# untitled.net
KiCad netlist of a schematic drawn in EAGLE
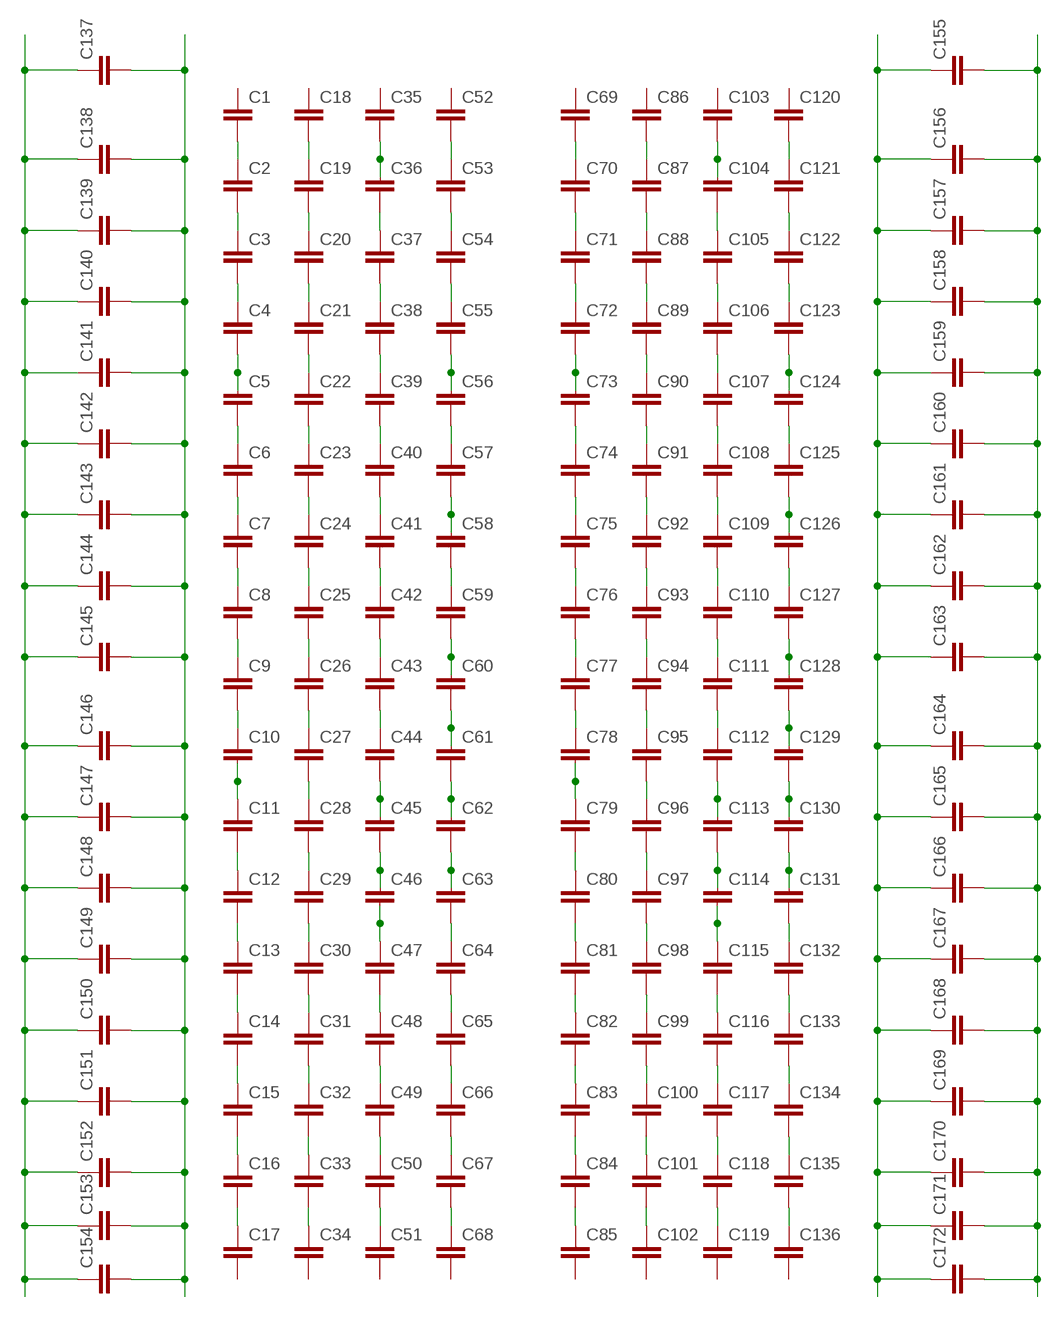
[diagram p0: schematic, sheet 1]

(export (version "E")
  (design (tool "Eeschema 10.0.6"))
  (components
    (comp (ref "C1")
      (value "C2,5-3")
      (footprint "eagle-import:C2.5-3")
      (libsource (lib "eagle-import") (part "C2,5-3"))
    )
    (comp (ref "C2")
      (value "C2,5-3")
      (footprint "eagle-import:C2.5-3")
      (libsource (lib "eagle-import") (part "C2,5-3"))
    )
    (comp (ref "C3")
      (value "C2,5-3")
      (footprint "eagle-import:C2.5-3")
      (libsource (lib "eagle-import") (part "C2,5-3"))
    )
    (comp (ref "C4")
      (value "C2,5-3")
      (footprint "eagle-import:C2.5-3")
      (libsource (lib "eagle-import") (part "C2,5-3"))
    )
    (comp (ref "C5")
      (value "C2,5-3")
      (footprint "eagle-import:C2.5-3")
      (libsource (lib "eagle-import") (part "C2,5-3"))
    )
    (comp (ref "C6")
      (value "C2,5-3")
      (footprint "eagle-import:C2.5-3")
      (libsource (lib "eagle-import") (part "C2,5-3"))
    )
    (comp (ref "C7")
      (value "C2,5-3")
      (footprint "eagle-import:C2.5-3")
      (libsource (lib "eagle-import") (part "C2,5-3"))
    )
    (comp (ref "C8")
      (value "C2,5-3")
      (footprint "eagle-import:C2.5-3")
      (libsource (lib "eagle-import") (part "C2,5-3"))
    )
    (comp (ref "C9")
      (value "C2,5-3")
      (footprint "eagle-import:C2.5-3")
      (libsource (lib "eagle-import") (part "C2,5-3"))
    )
    (comp (ref "C10")
      (value "C2,5-3")
      (footprint "eagle-import:C2.5-3")
      (libsource (lib "eagle-import") (part "C2,5-3"))
    )
    (comp (ref "C11")
      (value "C2,5-3")
      (footprint "eagle-import:C2.5-3")
      (libsource (lib "eagle-import") (part "C2,5-3"))
    )
    (comp (ref "C12")
      (value "C2,5-3")
      (footprint "eagle-import:C2.5-3")
      (libsource (lib "eagle-import") (part "C2,5-3"))
    )
    (comp (ref "C13")
      (value "C2,5-3")
      (footprint "eagle-import:C2.5-3")
      (libsource (lib "eagle-import") (part "C2,5-3"))
    )
    (comp (ref "C14")
      (value "C2,5-3")
      (footprint "eagle-import:C2.5-3")
      (libsource (lib "eagle-import") (part "C2,5-3"))
    )
    (comp (ref "C15")
      (value "C2,5-3")
      (footprint "eagle-import:C2.5-3")
      (libsource (lib "eagle-import") (part "C2,5-3"))
    )
    (comp (ref "C16")
      (value "C2,5-3")
      (footprint "eagle-import:C2.5-3")
      (libsource (lib "eagle-import") (part "C2,5-3"))
    )
    (comp (ref "C17")
      (value "C2,5-3")
      (footprint "eagle-import:C2.5-3")
      (libsource (lib "eagle-import") (part "C2,5-3"))
    )
    (comp (ref "C18")
      (value "C2,5-3")
      (footprint "eagle-import:C2.5-3")
      (libsource (lib "eagle-import") (part "C2,5-3"))
    )
    (comp (ref "C19")
      (value "C2,5-3")
      (footprint "eagle-import:C2.5-3")
      (libsource (lib "eagle-import") (part "C2,5-3"))
    )
    (comp (ref "C20")
      (value "C2,5-3")
      (footprint "eagle-import:C2.5-3")
      (libsource (lib "eagle-import") (part "C2,5-3"))
    )
    (comp (ref "C21")
      (value "C2,5-3")
      (footprint "eagle-import:C2.5-3")
      (libsource (lib "eagle-import") (part "C2,5-3"))
    )
    (comp (ref "C22")
      (value "C2,5-3")
      (footprint "eagle-import:C2.5-3")
      (libsource (lib "eagle-import") (part "C2,5-3"))
    )
    (comp (ref "C23")
      (value "C2,5-3")
      (footprint "eagle-import:C2.5-3")
      (libsource (lib "eagle-import") (part "C2,5-3"))
    )
    (comp (ref "C24")
      (value "C2,5-3")
      (footprint "eagle-import:C2.5-3")
      (libsource (lib "eagle-import") (part "C2,5-3"))
    )
    (comp (ref "C25")
      (value "C2,5-3")
      (footprint "eagle-import:C2.5-3")
      (libsource (lib "eagle-import") (part "C2,5-3"))
    )
    (comp (ref "C26")
      (value "C2,5-3")
      (footprint "eagle-import:C2.5-3")
      (libsource (lib "eagle-import") (part "C2,5-3"))
    )
    (comp (ref "C27")
      (value "C2,5-3")
      (footprint "eagle-import:C2.5-3")
      (libsource (lib "eagle-import") (part "C2,5-3"))
    )
    (comp (ref "C28")
      (value "C2,5-3")
      (footprint "eagle-import:C2.5-3")
      (libsource (lib "eagle-import") (part "C2,5-3"))
    )
    (comp (ref "C29")
      (value "C2,5-3")
      (footprint "eagle-import:C2.5-3")
      (libsource (lib "eagle-import") (part "C2,5-3"))
    )
    (comp (ref "C30")
      (value "C2,5-3")
      (footprint "eagle-import:C2.5-3")
      (libsource (lib "eagle-import") (part "C2,5-3"))
    )
    (comp (ref "C31")
      (value "C2,5-3")
      (footprint "eagle-import:C2.5-3")
      (libsource (lib "eagle-import") (part "C2,5-3"))
    )
    (comp (ref "C32")
      (value "C2,5-3")
      (footprint "eagle-import:C2.5-3")
      (libsource (lib "eagle-import") (part "C2,5-3"))
    )
    (comp (ref "C33")
      (value "C2,5-3")
      (footprint "eagle-import:C2.5-3")
      (libsource (lib "eagle-import") (part "C2,5-3"))
    )
    (comp (ref "C34")
      (value "C2,5-3")
      (footprint "eagle-import:C2.5-3")
      (libsource (lib "eagle-import") (part "C2,5-3"))
    )
    (comp (ref "C35")
      (value "C2,5-3")
      (footprint "eagle-import:C2.5-3")
      (libsource (lib "eagle-import") (part "C2,5-3"))
    )
    (comp (ref "C36")
      (value "C2,5-3")
      (footprint "eagle-import:C2.5-3")
      (libsource (lib "eagle-import") (part "C2,5-3"))
    )
    (comp (ref "C37")
      (value "C2,5-3")
      (footprint "eagle-import:C2.5-3")
      (libsource (lib "eagle-import") (part "C2,5-3"))
    )
    (comp (ref "C38")
      (value "C2,5-3")
      (footprint "eagle-import:C2.5-3")
      (libsource (lib "eagle-import") (part "C2,5-3"))
    )
    (comp (ref "C39")
      (value "C2,5-3")
      (footprint "eagle-import:C2.5-3")
      (libsource (lib "eagle-import") (part "C2,5-3"))
    )
    (comp (ref "C40")
      (value "C2,5-3")
      (footprint "eagle-import:C2.5-3")
      (libsource (lib "eagle-import") (part "C2,5-3"))
    )
    (comp (ref "C41")
      (value "C2,5-3")
      (footprint "eagle-import:C2.5-3")
      (libsource (lib "eagle-import") (part "C2,5-3"))
    )
    (comp (ref "C42")
      (value "C2,5-3")
      (footprint "eagle-import:C2.5-3")
      (libsource (lib "eagle-import") (part "C2,5-3"))
    )
    (comp (ref "C43")
      (value "C2,5-3")
      (footprint "eagle-import:C2.5-3")
      (libsource (lib "eagle-import") (part "C2,5-3"))
    )
    (comp (ref "C44")
      (value "C2,5-3")
      (footprint "eagle-import:C2.5-3")
      (libsource (lib "eagle-import") (part "C2,5-3"))
    )
    (comp (ref "C45")
      (value "C2,5-3")
      (footprint "eagle-import:C2.5-3")
      (libsource (lib "eagle-import") (part "C2,5-3"))
    )
    (comp (ref "C46")
      (value "C2,5-3")
      (footprint "eagle-import:C2.5-3")
      (libsource (lib "eagle-import") (part "C2,5-3"))
    )
    (comp (ref "C47")
      (value "C2,5-3")
      (footprint "eagle-import:C2.5-3")
      (libsource (lib "eagle-import") (part "C2,5-3"))
    )
    (comp (ref "C48")
      (value "C2,5-3")
      (footprint "eagle-import:C2.5-3")
      (libsource (lib "eagle-import") (part "C2,5-3"))
    )
    (comp (ref "C49")
      (value "C2,5-3")
      (footprint "eagle-import:C2.5-3")
      (libsource (lib "eagle-import") (part "C2,5-3"))
    )
    (comp (ref "C50")
      (value "C2,5-3")
      (footprint "eagle-import:C2.5-3")
      (libsource (lib "eagle-import") (part "C2,5-3"))
    )
    (comp (ref "C51")
      (value "C2,5-3")
      (footprint "eagle-import:C2.5-3")
      (libsource (lib "eagle-import") (part "C2,5-3"))
    )
    (comp (ref "C52")
      (value "C2,5-3")
      (footprint "eagle-import:C2.5-3")
      (libsource (lib "eagle-import") (part "C2,5-3"))
    )
    (comp (ref "C53")
      (value "C2,5-3")
      (footprint "eagle-import:C2.5-3")
      (libsource (lib "eagle-import") (part "C2,5-3"))
    )
    (comp (ref "C54")
      (value "C2,5-3")
      (footprint "eagle-import:C2.5-3")
      (libsource (lib "eagle-import") (part "C2,5-3"))
    )
    (comp (ref "C55")
      (value "C2,5-3")
      (footprint "eagle-import:C2.5-3")
      (libsource (lib "eagle-import") (part "C2,5-3"))
    )
    (comp (ref "C56")
      (value "C2,5-3")
      (footprint "eagle-import:C2.5-3")
      (libsource (lib "eagle-import") (part "C2,5-3"))
    )
    (comp (ref "C57")
      (value "C2,5-3")
      (footprint "eagle-import:C2.5-3")
      (libsource (lib "eagle-import") (part "C2,5-3"))
    )
    (comp (ref "C58")
      (value "C2,5-3")
      (footprint "eagle-import:C2.5-3")
      (libsource (lib "eagle-import") (part "C2,5-3"))
    )
    (comp (ref "C59")
      (value "C2,5-3")
      (footprint "eagle-import:C2.5-3")
      (libsource (lib "eagle-import") (part "C2,5-3"))
    )
    (comp (ref "C60")
      (value "C2,5-3")
      (footprint "eagle-import:C2.5-3")
      (libsource (lib "eagle-import") (part "C2,5-3"))
    )
    (comp (ref "C61")
      (value "C2,5-3")
      (footprint "eagle-import:C2.5-3")
      (libsource (lib "eagle-import") (part "C2,5-3"))
    )
    (comp (ref "C62")
      (value "C2,5-3")
      (footprint "eagle-import:C2.5-3")
      (libsource (lib "eagle-import") (part "C2,5-3"))
    )
    (comp (ref "C63")
      (value "C2,5-3")
      (footprint "eagle-import:C2.5-3")
      (libsource (lib "eagle-import") (part "C2,5-3"))
    )
    (comp (ref "C64")
      (value "C2,5-3")
      (footprint "eagle-import:C2.5-3")
      (libsource (lib "eagle-import") (part "C2,5-3"))
    )
    (comp (ref "C65")
      (value "C2,5-3")
      (footprint "eagle-import:C2.5-3")
      (libsource (lib "eagle-import") (part "C2,5-3"))
    )
    (comp (ref "C66")
      (value "C2,5-3")
      (footprint "eagle-import:C2.5-3")
      (libsource (lib "eagle-import") (part "C2,5-3"))
    )
    (comp (ref "C67")
      (value "C2,5-3")
      (footprint "eagle-import:C2.5-3")
      (libsource (lib "eagle-import") (part "C2,5-3"))
    )
    (comp (ref "C68")
      (value "C2,5-3")
      (footprint "eagle-import:C2.5-3")
      (libsource (lib "eagle-import") (part "C2,5-3"))
    )
    (comp (ref "C69")
      (value "C2,5-3")
      (footprint "eagle-import:C2.5-3")
      (libsource (lib "eagle-import") (part "C2,5-3"))
    )
    (comp (ref "C70")
      (value "C2,5-3")
      (footprint "eagle-import:C2.5-3")
      (libsource (lib "eagle-import") (part "C2,5-3"))
    )
    (comp (ref "C71")
      (value "C2,5-3")
      (footprint "eagle-import:C2.5-3")
      (libsource (lib "eagle-import") (part "C2,5-3"))
    )
    (comp (ref "C72")
      (value "C2,5-3")
      (footprint "eagle-import:C2.5-3")
      (libsource (lib "eagle-import") (part "C2,5-3"))
    )
    (comp (ref "C73")
      (value "C2,5-3")
      (footprint "eagle-import:C2.5-3")
      (libsource (lib "eagle-import") (part "C2,5-3"))
    )
    (comp (ref "C74")
      (value "C2,5-3")
      (footprint "eagle-import:C2.5-3")
      (libsource (lib "eagle-import") (part "C2,5-3"))
    )
    (comp (ref "C75")
      (value "C2,5-3")
      (footprint "eagle-import:C2.5-3")
      (libsource (lib "eagle-import") (part "C2,5-3"))
    )
    (comp (ref "C76")
      (value "C2,5-3")
      (footprint "eagle-import:C2.5-3")
      (libsource (lib "eagle-import") (part "C2,5-3"))
    )
    (comp (ref "C77")
      (value "C2,5-3")
      (footprint "eagle-import:C2.5-3")
      (libsource (lib "eagle-import") (part "C2,5-3"))
    )
    (comp (ref "C78")
      (value "C2,5-3")
      (footprint "eagle-import:C2.5-3")
      (libsource (lib "eagle-import") (part "C2,5-3"))
    )
    (comp (ref "C79")
      (value "C2,5-3")
      (footprint "eagle-import:C2.5-3")
      (libsource (lib "eagle-import") (part "C2,5-3"))
    )
    (comp (ref "C80")
      (value "C2,5-3")
      (footprint "eagle-import:C2.5-3")
      (libsource (lib "eagle-import") (part "C2,5-3"))
    )
    (comp (ref "C81")
      (value "C2,5-3")
      (footprint "eagle-import:C2.5-3")
      (libsource (lib "eagle-import") (part "C2,5-3"))
    )
    (comp (ref "C82")
      (value "C2,5-3")
      (footprint "eagle-import:C2.5-3")
      (libsource (lib "eagle-import") (part "C2,5-3"))
    )
    (comp (ref "C83")
      (value "C2,5-3")
      (footprint "eagle-import:C2.5-3")
      (libsource (lib "eagle-import") (part "C2,5-3"))
    )
    (comp (ref "C84")
      (value "C2,5-3")
      (footprint "eagle-import:C2.5-3")
      (libsource (lib "eagle-import") (part "C2,5-3"))
    )
    (comp (ref "C85")
      (value "C2,5-3")
      (footprint "eagle-import:C2.5-3")
      (libsource (lib "eagle-import") (part "C2,5-3"))
    )
    (comp (ref "C86")
      (value "C2,5-3")
      (footprint "eagle-import:C2.5-3")
      (libsource (lib "eagle-import") (part "C2,5-3"))
    )
    (comp (ref "C87")
      (value "C2,5-3")
      (footprint "eagle-import:C2.5-3")
      (libsource (lib "eagle-import") (part "C2,5-3"))
    )
    (comp (ref "C88")
      (value "C2,5-3")
      (footprint "eagle-import:C2.5-3")
      (libsource (lib "eagle-import") (part "C2,5-3"))
    )
    (comp (ref "C89")
      (value "C2,5-3")
      (footprint "eagle-import:C2.5-3")
      (libsource (lib "eagle-import") (part "C2,5-3"))
    )
    (comp (ref "C90")
      (value "C2,5-3")
      (footprint "eagle-import:C2.5-3")
      (libsource (lib "eagle-import") (part "C2,5-3"))
    )
    (comp (ref "C91")
      (value "C2,5-3")
      (footprint "eagle-import:C2.5-3")
      (libsource (lib "eagle-import") (part "C2,5-3"))
    )
    (comp (ref "C92")
      (value "C2,5-3")
      (footprint "eagle-import:C2.5-3")
      (libsource (lib "eagle-import") (part "C2,5-3"))
    )
    (comp (ref "C93")
      (value "C2,5-3")
      (footprint "eagle-import:C2.5-3")
      (libsource (lib "eagle-import") (part "C2,5-3"))
    )
    (comp (ref "C94")
      (value "C2,5-3")
      (footprint "eagle-import:C2.5-3")
      (libsource (lib "eagle-import") (part "C2,5-3"))
    )
    (comp (ref "C95")
      (value "C2,5-3")
      (footprint "eagle-import:C2.5-3")
      (libsource (lib "eagle-import") (part "C2,5-3"))
    )
    (comp (ref "C96")
      (value "C2,5-3")
      (footprint "eagle-import:C2.5-3")
      (libsource (lib "eagle-import") (part "C2,5-3"))
    )
    (comp (ref "C97")
      (value "C2,5-3")
      (footprint "eagle-import:C2.5-3")
      (libsource (lib "eagle-import") (part "C2,5-3"))
    )
    (comp (ref "C98")
      (value "C2,5-3")
      (footprint "eagle-import:C2.5-3")
      (libsource (lib "eagle-import") (part "C2,5-3"))
    )
    (comp (ref "C99")
      (value "C2,5-3")
      (footprint "eagle-import:C2.5-3")
      (libsource (lib "eagle-import") (part "C2,5-3"))
    )
    (comp (ref "C100")
      (value "C2,5-3")
      (footprint "eagle-import:C2.5-3")
      (libsource (lib "eagle-import") (part "C2,5-3"))
    )
    (comp (ref "C101")
      (value "C2,5-3")
      (footprint "eagle-import:C2.5-3")
      (libsource (lib "eagle-import") (part "C2,5-3"))
    )
    (comp (ref "C102")
      (value "C2,5-3")
      (footprint "eagle-import:C2.5-3")
      (libsource (lib "eagle-import") (part "C2,5-3"))
    )
    (comp (ref "C103")
      (value "C2,5-3")
      (footprint "eagle-import:C2.5-3")
      (libsource (lib "eagle-import") (part "C2,5-3"))
    )
    (comp (ref "C104")
      (value "C2,5-3")
      (footprint "eagle-import:C2.5-3")
      (libsource (lib "eagle-import") (part "C2,5-3"))
    )
    (comp (ref "C105")
      (value "C2,5-3")
      (footprint "eagle-import:C2.5-3")
      (libsource (lib "eagle-import") (part "C2,5-3"))
    )
    (comp (ref "C106")
      (value "C2,5-3")
      (footprint "eagle-import:C2.5-3")
      (libsource (lib "eagle-import") (part "C2,5-3"))
    )
    (comp (ref "C107")
      (value "C2,5-3")
      (footprint "eagle-import:C2.5-3")
      (libsource (lib "eagle-import") (part "C2,5-3"))
    )
    (comp (ref "C108")
      (value "C2,5-3")
      (footprint "eagle-import:C2.5-3")
      (libsource (lib "eagle-import") (part "C2,5-3"))
    )
    (comp (ref "C109")
      (value "C2,5-3")
      (footprint "eagle-import:C2.5-3")
      (libsource (lib "eagle-import") (part "C2,5-3"))
    )
    (comp (ref "C110")
      (value "C2,5-3")
      (footprint "eagle-import:C2.5-3")
      (libsource (lib "eagle-import") (part "C2,5-3"))
    )
    (comp (ref "C111")
      (value "C2,5-3")
      (footprint "eagle-import:C2.5-3")
      (libsource (lib "eagle-import") (part "C2,5-3"))
    )
    (comp (ref "C112")
      (value "C2,5-3")
      (footprint "eagle-import:C2.5-3")
      (libsource (lib "eagle-import") (part "C2,5-3"))
    )
    (comp (ref "C113")
      (value "C2,5-3")
      (footprint "eagle-import:C2.5-3")
      (libsource (lib "eagle-import") (part "C2,5-3"))
    )
    (comp (ref "C114")
      (value "C2,5-3")
      (footprint "eagle-import:C2.5-3")
      (libsource (lib "eagle-import") (part "C2,5-3"))
    )
    (comp (ref "C115")
      (value "C2,5-3")
      (footprint "eagle-import:C2.5-3")
      (libsource (lib "eagle-import") (part "C2,5-3"))
    )
    (comp (ref "C116")
      (value "C2,5-3")
      (footprint "eagle-import:C2.5-3")
      (libsource (lib "eagle-import") (part "C2,5-3"))
    )
    (comp (ref "C117")
      (value "C2,5-3")
      (footprint "eagle-import:C2.5-3")
      (libsource (lib "eagle-import") (part "C2,5-3"))
    )
    (comp (ref "C118")
      (value "C2,5-3")
      (footprint "eagle-import:C2.5-3")
      (libsource (lib "eagle-import") (part "C2,5-3"))
    )
    (comp (ref "C119")
      (value "C2,5-3")
      (footprint "eagle-import:C2.5-3")
      (libsource (lib "eagle-import") (part "C2,5-3"))
    )
    (comp (ref "C120")
      (value "C2,5-3")
      (footprint "eagle-import:C2.5-3")
      (libsource (lib "eagle-import") (part "C2,5-3"))
    )
    (comp (ref "C121")
      (value "C2,5-3")
      (footprint "eagle-import:C2.5-3")
      (libsource (lib "eagle-import") (part "C2,5-3"))
    )
    (comp (ref "C122")
      (value "C2,5-3")
      (footprint "eagle-import:C2.5-3")
      (libsource (lib "eagle-import") (part "C2,5-3"))
    )
    (comp (ref "C123")
      (value "C2,5-3")
      (footprint "eagle-import:C2.5-3")
      (libsource (lib "eagle-import") (part "C2,5-3"))
    )
    (comp (ref "C124")
      (value "C2,5-3")
      (footprint "eagle-import:C2.5-3")
      (libsource (lib "eagle-import") (part "C2,5-3"))
    )
    (comp (ref "C125")
      (value "C2,5-3")
      (footprint "eagle-import:C2.5-3")
      (libsource (lib "eagle-import") (part "C2,5-3"))
    )
    (comp (ref "C126")
      (value "C2,5-3")
      (footprint "eagle-import:C2.5-3")
      (libsource (lib "eagle-import") (part "C2,5-3"))
    )
    (comp (ref "C127")
      (value "C2,5-3")
      (footprint "eagle-import:C2.5-3")
      (libsource (lib "eagle-import") (part "C2,5-3"))
    )
    (comp (ref "C128")
      (value "C2,5-3")
      (footprint "eagle-import:C2.5-3")
      (libsource (lib "eagle-import") (part "C2,5-3"))
    )
    (comp (ref "C129")
      (value "C2,5-3")
      (footprint "eagle-import:C2.5-3")
      (libsource (lib "eagle-import") (part "C2,5-3"))
    )
    (comp (ref "C130")
      (value "C2,5-3")
      (footprint "eagle-import:C2.5-3")
      (libsource (lib "eagle-import") (part "C2,5-3"))
    )
    (comp (ref "C131")
      (value "C2,5-3")
      (footprint "eagle-import:C2.5-3")
      (libsource (lib "eagle-import") (part "C2,5-3"))
    )
    (comp (ref "C132")
      (value "C2,5-3")
      (footprint "eagle-import:C2.5-3")
      (libsource (lib "eagle-import") (part "C2,5-3"))
    )
    (comp (ref "C133")
      (value "C2,5-3")
      (footprint "eagle-import:C2.5-3")
      (libsource (lib "eagle-import") (part "C2,5-3"))
    )
    (comp (ref "C134")
      (value "C2,5-3")
      (footprint "eagle-import:C2.5-3")
      (libsource (lib "eagle-import") (part "C2,5-3"))
    )
    (comp (ref "C135")
      (value "C2,5-3")
      (footprint "eagle-import:C2.5-3")
      (libsource (lib "eagle-import") (part "C2,5-3"))
    )
    (comp (ref "C136")
      (value "C2,5-3")
      (footprint "eagle-import:C2.5-3")
      (libsource (lib "eagle-import") (part "C2,5-3"))
    )
    (comp (ref "C137")
      (value "C2,5-3")
      (footprint "eagle-import:C2.5-3")
      (libsource (lib "eagle-import") (part "C2,5-3"))
    )
    (comp (ref "C138")
      (value "C2,5-3")
      (footprint "eagle-import:C2.5-3")
      (libsource (lib "eagle-import") (part "C2,5-3"))
    )
    (comp (ref "C139")
      (value "C2,5-3")
      (footprint "eagle-import:C2.5-3")
      (libsource (lib "eagle-import") (part "C2,5-3"))
    )
    (comp (ref "C140")
      (value "C2,5-3")
      (footprint "eagle-import:C2.5-3")
      (libsource (lib "eagle-import") (part "C2,5-3"))
    )
    (comp (ref "C141")
      (value "C2,5-3")
      (footprint "eagle-import:C2.5-3")
      (libsource (lib "eagle-import") (part "C2,5-3"))
    )
    (comp (ref "C142")
      (value "C2,5-3")
      (footprint "eagle-import:C2.5-3")
      (libsource (lib "eagle-import") (part "C2,5-3"))
    )
    (comp (ref "C143")
      (value "C2,5-3")
      (footprint "eagle-import:C2.5-3")
      (libsource (lib "eagle-import") (part "C2,5-3"))
    )
    (comp (ref "C144")
      (value "C2,5-3")
      (footprint "eagle-import:C2.5-3")
      (libsource (lib "eagle-import") (part "C2,5-3"))
    )
    (comp (ref "C145")
      (value "C2,5-3")
      (footprint "eagle-import:C2.5-3")
      (libsource (lib "eagle-import") (part "C2,5-3"))
    )
    (comp (ref "C146")
      (value "C2,5-3")
      (footprint "eagle-import:C2.5-3")
      (libsource (lib "eagle-import") (part "C2,5-3"))
    )
    (comp (ref "C147")
      (value "C2,5-3")
      (footprint "eagle-import:C2.5-3")
      (libsource (lib "eagle-import") (part "C2,5-3"))
    )
    (comp (ref "C148")
      (value "C2,5-3")
      (footprint "eagle-import:C2.5-3")
      (libsource (lib "eagle-import") (part "C2,5-3"))
    )
    (comp (ref "C149")
      (value "C2,5-3")
      (footprint "eagle-import:C2.5-3")
      (libsource (lib "eagle-import") (part "C2,5-3"))
    )
    (comp (ref "C150")
      (value "C2,5-3")
      (footprint "eagle-import:C2.5-3")
      (libsource (lib "eagle-import") (part "C2,5-3"))
    )
    (comp (ref "C151")
      (value "C2,5-3")
      (footprint "eagle-import:C2.5-3")
      (libsource (lib "eagle-import") (part "C2,5-3"))
    )
    (comp (ref "C152")
      (value "C2,5-3")
      (footprint "eagle-import:C2.5-3")
      (libsource (lib "eagle-import") (part "C2,5-3"))
    )
    (comp (ref "C153")
      (value "C2,5-3")
      (footprint "eagle-import:C2.5-3")
      (libsource (lib "eagle-import") (part "C2,5-3"))
    )
    (comp (ref "C154")
      (value "C2,5-3")
      (footprint "eagle-import:C2.5-3")
      (libsource (lib "eagle-import") (part "C2,5-3"))
    )
    (comp (ref "C155")
      (value "C2,5-3")
      (footprint "eagle-import:C2.5-3")
      (libsource (lib "eagle-import") (part "C2,5-3"))
    )
    (comp (ref "C156")
      (value "C2,5-3")
      (footprint "eagle-import:C2.5-3")
      (libsource (lib "eagle-import") (part "C2,5-3"))
    )
    (comp (ref "C157")
      (value "C2,5-3")
      (footprint "eagle-import:C2.5-3")
      (libsource (lib "eagle-import") (part "C2,5-3"))
    )
    (comp (ref "C158")
      (value "C2,5-3")
      (footprint "eagle-import:C2.5-3")
      (libsource (lib "eagle-import") (part "C2,5-3"))
    )
    (comp (ref "C159")
      (value "C2,5-3")
      (footprint "eagle-import:C2.5-3")
      (libsource (lib "eagle-import") (part "C2,5-3"))
    )
    (comp (ref "C160")
      (value "C2,5-3")
      (footprint "eagle-import:C2.5-3")
      (libsource (lib "eagle-import") (part "C2,5-3"))
    )
    (comp (ref "C161")
      (value "C2,5-3")
      (footprint "eagle-import:C2.5-3")
      (libsource (lib "eagle-import") (part "C2,5-3"))
    )
    (comp (ref "C162")
      (value "C2,5-3")
      (footprint "eagle-import:C2.5-3")
      (libsource (lib "eagle-import") (part "C2,5-3"))
    )
    (comp (ref "C163")
      (value "C2,5-3")
      (footprint "eagle-import:C2.5-3")
      (libsource (lib "eagle-import") (part "C2,5-3"))
    )
    (comp (ref "C164")
      (value "C2,5-3")
      (footprint "eagle-import:C2.5-3")
      (libsource (lib "eagle-import") (part "C2,5-3"))
    )
    (comp (ref "C165")
      (value "C2,5-3")
      (footprint "eagle-import:C2.5-3")
      (libsource (lib "eagle-import") (part "C2,5-3"))
    )
    (comp (ref "C166")
      (value "C2,5-3")
      (footprint "eagle-import:C2.5-3")
      (libsource (lib "eagle-import") (part "C2,5-3"))
    )
    (comp (ref "C167")
      (value "C2,5-3")
      (footprint "eagle-import:C2.5-3")
      (libsource (lib "eagle-import") (part "C2,5-3"))
    )
    (comp (ref "C168")
      (value "C2,5-3")
      (footprint "eagle-import:C2.5-3")
      (libsource (lib "eagle-import") (part "C2,5-3"))
    )
    (comp (ref "C169")
      (value "C2,5-3")
      (footprint "eagle-import:C2.5-3")
      (libsource (lib "eagle-import") (part "C2,5-3"))
    )
    (comp (ref "C170")
      (value "C2,5-3")
      (footprint "eagle-import:C2.5-3")
      (libsource (lib "eagle-import") (part "C2,5-3"))
    )
    (comp (ref "C171")
      (value "C2,5-3")
      (footprint "eagle-import:C2.5-3")
      (libsource (lib "eagle-import") (part "C2,5-3"))
    )
    (comp (ref "C172")
      (value "C2,5-3")
      (footprint "eagle-import:C2.5-3")
      (libsource (lib "eagle-import") (part "C2,5-3"))
    )
  )
  (nets
    (net (code "1") (name "Net-(C1-Pad2)") (class "Default")
      (node (ref "C1") (pin "2") (pinfunction "2_2") (pintype "passive"))
      (node (ref "C2") (pin "1") (pinfunction "1_1") (pintype "passive"))
    )
    (net (code "2") (name "Net-(C2-Pad2)") (class "Default")
      (node (ref "C2") (pin "2") (pinfunction "2_2") (pintype "passive"))
      (node (ref "C3") (pin "1") (pinfunction "1_1") (pintype "passive"))
    )
    (net (code "3") (name "Net-(C3-Pad2)") (class "Default")
      (node (ref "C3") (pin "2") (pinfunction "2_2") (pintype "passive"))
      (node (ref "C4") (pin "1") (pinfunction "1_1") (pintype "passive"))
    )
    (net (code "4") (name "Net-(C4-Pad2)") (class "Default")
      (node (ref "C4") (pin "2") (pinfunction "2_2") (pintype "passive"))
      (node (ref "C5") (pin "1") (pinfunction "1_1") (pintype "passive"))
    )
    (net (code "5") (name "Net-(C5-Pad2)") (class "Default")
      (node (ref "C5") (pin "2") (pinfunction "2_2") (pintype "passive"))
      (node (ref "C6") (pin "1") (pinfunction "1_1") (pintype "passive"))
    )
    (net (code "6") (name "Net-(C6-Pad2)") (class "Default")
      (node (ref "C6") (pin "2") (pinfunction "2_2") (pintype "passive"))
      (node (ref "C7") (pin "1") (pinfunction "1_1") (pintype "passive"))
    )
    (net (code "7") (name "Net-(C7-Pad2)") (class "Default")
      (node (ref "C7") (pin "2") (pinfunction "2_2") (pintype "passive"))
      (node (ref "C8") (pin "1") (pinfunction "1_1") (pintype "passive"))
    )
    (net (code "8") (name "Net-(C8-Pad2)") (class "Default")
      (node (ref "C8") (pin "2") (pinfunction "2_2") (pintype "passive"))
      (node (ref "C9") (pin "1") (pinfunction "1_1") (pintype "passive"))
    )
    (net (code "9") (name "Net-(C10-Pad1)") (class "Default")
      (node (ref "C10") (pin "1") (pinfunction "1_1") (pintype "passive"))
      (node (ref "C9") (pin "2") (pinfunction "2_2") (pintype "passive"))
    )
    (net (code "10") (name "Net-(C10-Pad2)") (class "Default")
      (node (ref "C10") (pin "2") (pinfunction "2_2") (pintype "passive"))
      (node (ref "C11") (pin "1") (pinfunction "1_1") (pintype "passive"))
    )
    (net (code "11") (name "Net-(C11-Pad2)") (class "Default")
      (node (ref "C11") (pin "2") (pinfunction "2_2") (pintype "passive"))
      (node (ref "C12") (pin "1") (pinfunction "1_1") (pintype "passive"))
    )
    (net (code "12") (name "Net-(C12-Pad2)") (class "Default")
      (node (ref "C12") (pin "2") (pinfunction "2_2") (pintype "passive"))
      (node (ref "C13") (pin "1") (pinfunction "1_1") (pintype "passive"))
    )
    (net (code "13") (name "Net-(C13-Pad2)") (class "Default")
      (node (ref "C13") (pin "2") (pinfunction "2_2") (pintype "passive"))
      (node (ref "C14") (pin "1") (pinfunction "1_1") (pintype "passive"))
    )
    (net (code "14") (name "Net-(C14-Pad2)") (class "Default")
      (node (ref "C14") (pin "2") (pinfunction "2_2") (pintype "passive"))
      (node (ref "C15") (pin "1") (pinfunction "1_1") (pintype "passive"))
    )
    (net (code "15") (name "Net-(C15-Pad2)") (class "Default")
      (node (ref "C15") (pin "2") (pinfunction "2_2") (pintype "passive"))
      (node (ref "C16") (pin "1") (pinfunction "1_1") (pintype "passive"))
    )
    (net (code "16") (name "Net-(C16-Pad2)") (class "Default")
      (node (ref "C16") (pin "2") (pinfunction "2_2") (pintype "passive"))
      (node (ref "C17") (pin "1") (pinfunction "1_1") (pintype "passive"))
    )
    (net (code "17") (name "Net-(C18-Pad2)") (class "Default")
      (node (ref "C18") (pin "2") (pinfunction "2_2") (pintype "passive"))
      (node (ref "C19") (pin "1") (pinfunction "1_1") (pintype "passive"))
    )
    (net (code "18") (name "Net-(C19-Pad2)") (class "Default")
      (node (ref "C19") (pin "2") (pinfunction "2_2") (pintype "passive"))
      (node (ref "C20") (pin "1") (pinfunction "1_1") (pintype "passive"))
    )
    (net (code "19") (name "Net-(C20-Pad2)") (class "Default")
      (node (ref "C20") (pin "2") (pinfunction "2_2") (pintype "passive"))
      (node (ref "C21") (pin "1") (pinfunction "1_1") (pintype "passive"))
    )
    (net (code "20") (name "Net-(C21-Pad2)") (class "Default")
      (node (ref "C21") (pin "2") (pinfunction "2_2") (pintype "passive"))
      (node (ref "C22") (pin "1") (pinfunction "1_1") (pintype "passive"))
    )
    (net (code "21") (name "Net-(C22-Pad2)") (class "Default")
      (node (ref "C22") (pin "2") (pinfunction "2_2") (pintype "passive"))
      (node (ref "C23") (pin "1") (pinfunction "1_1") (pintype "passive"))
    )
    (net (code "22") (name "Net-(C23-Pad2)") (class "Default")
      (node (ref "C23") (pin "2") (pinfunction "2_2") (pintype "passive"))
      (node (ref "C24") (pin "1") (pinfunction "1_1") (pintype "passive"))
    )
    (net (code "23") (name "Net-(C24-Pad2)") (class "Default")
      (node (ref "C24") (pin "2") (pinfunction "2_2") (pintype "passive"))
      (node (ref "C25") (pin "1") (pinfunction "1_1") (pintype "passive"))
    )
    (net (code "24") (name "Net-(C25-Pad2)") (class "Default")
      (node (ref "C25") (pin "2") (pinfunction "2_2") (pintype "passive"))
      (node (ref "C26") (pin "1") (pinfunction "1_1") (pintype "passive"))
    )
    (net (code "25") (name "Net-(C26-Pad2)") (class "Default")
      (node (ref "C26") (pin "2") (pinfunction "2_2") (pintype "passive"))
      (node (ref "C27") (pin "1") (pinfunction "1_1") (pintype "passive"))
    )
    (net (code "26") (name "Net-(C27-Pad2)") (class "Default")
      (node (ref "C27") (pin "2") (pinfunction "2_2") (pintype "passive"))
      (node (ref "C28") (pin "1") (pinfunction "1_1") (pintype "passive"))
    )
    (net (code "27") (name "Net-(C28-Pad2)") (class "Default")
      (node (ref "C28") (pin "2") (pinfunction "2_2") (pintype "passive"))
      (node (ref "C29") (pin "1") (pinfunction "1_1") (pintype "passive"))
    )
    (net (code "28") (name "Net-(C29-Pad2)") (class "Default")
      (node (ref "C29") (pin "2") (pinfunction "2_2") (pintype "passive"))
      (node (ref "C30") (pin "1") (pinfunction "1_1") (pintype "passive"))
    )
    (net (code "29") (name "Net-(C30-Pad2)") (class "Default")
      (node (ref "C30") (pin "2") (pinfunction "2_2") (pintype "passive"))
      (node (ref "C31") (pin "1") (pinfunction "1_1") (pintype "passive"))
    )
    (net (code "30") (name "Net-(C31-Pad2)") (class "Default")
      (node (ref "C31") (pin "2") (pinfunction "2_2") (pintype "passive"))
      (node (ref "C32") (pin "1") (pinfunction "1_1") (pintype "passive"))
    )
    (net (code "31") (name "Net-(C32-Pad2)") (class "Default")
      (node (ref "C32") (pin "2") (pinfunction "2_2") (pintype "passive"))
      (node (ref "C33") (pin "1") (pinfunction "1_1") (pintype "passive"))
    )
    (net (code "32") (name "Net-(C33-Pad2)") (class "Default")
      (node (ref "C33") (pin "2") (pinfunction "2_2") (pintype "passive"))
      (node (ref "C34") (pin "1") (pinfunction "1_1") (pintype "passive"))
    )
    (net (code "33") (name "Net-(C35-Pad2)") (class "Default")
      (node (ref "C35") (pin "2") (pinfunction "2_2") (pintype "passive"))
      (node (ref "C36") (pin "1") (pinfunction "1_1") (pintype "passive"))
    )
    (net (code "34") (name "Net-(C36-Pad2)") (class "Default")
      (node (ref "C36") (pin "2") (pinfunction "2_2") (pintype "passive"))
      (node (ref "C37") (pin "1") (pinfunction "1_1") (pintype "passive"))
    )
    (net (code "35") (name "Net-(C37-Pad2)") (class "Default")
      (node (ref "C37") (pin "2") (pinfunction "2_2") (pintype "passive"))
      (node (ref "C38") (pin "1") (pinfunction "1_1") (pintype "passive"))
    )
    (net (code "36") (name "Net-(C38-Pad2)") (class "Default")
      (node (ref "C38") (pin "2") (pinfunction "2_2") (pintype "passive"))
      (node (ref "C39") (pin "1") (pinfunction "1_1") (pintype "passive"))
    )
    (net (code "37") (name "Net-(C39-Pad2)") (class "Default")
      (node (ref "C39") (pin "2") (pinfunction "2_2") (pintype "passive"))
      (node (ref "C40") (pin "1") (pinfunction "1_1") (pintype "passive"))
    )
    (net (code "38") (name "Net-(C40-Pad2)") (class "Default")
      (node (ref "C40") (pin "2") (pinfunction "2_2") (pintype "passive"))
      (node (ref "C41") (pin "1") (pinfunction "1_1") (pintype "passive"))
    )
    (net (code "39") (name "Net-(C41-Pad2)") (class "Default")
      (node (ref "C41") (pin "2") (pinfunction "2_2") (pintype "passive"))
      (node (ref "C42") (pin "1") (pinfunction "1_1") (pintype "passive"))
    )
    (net (code "40") (name "Net-(C42-Pad2)") (class "Default")
      (node (ref "C42") (pin "2") (pinfunction "2_2") (pintype "passive"))
      (node (ref "C43") (pin "1") (pinfunction "1_1") (pintype "passive"))
    )
    (net (code "41") (name "Net-(C43-Pad2)") (class "Default")
      (node (ref "C43") (pin "2") (pinfunction "2_2") (pintype "passive"))
      (node (ref "C44") (pin "1") (pinfunction "1_1") (pintype "passive"))
    )
    (net (code "42") (name "Net-(C44-Pad2)") (class "Default")
      (node (ref "C44") (pin "2") (pinfunction "2_2") (pintype "passive"))
      (node (ref "C45") (pin "1") (pinfunction "1_1") (pintype "passive"))
    )
    (net (code "43") (name "Net-(C45-Pad2)") (class "Default")
      (node (ref "C45") (pin "2") (pinfunction "2_2") (pintype "passive"))
      (node (ref "C46") (pin "1") (pinfunction "1_1") (pintype "passive"))
    )
    (net (code "44") (name "Net-(C46-Pad2)") (class "Default")
      (node (ref "C46") (pin "2") (pinfunction "2_2") (pintype "passive"))
      (node (ref "C47") (pin "1") (pinfunction "1_1") (pintype "passive"))
    )
    (net (code "45") (name "Net-(C47-Pad2)") (class "Default")
      (node (ref "C47") (pin "2") (pinfunction "2_2") (pintype "passive"))
      (node (ref "C48") (pin "1") (pinfunction "1_1") (pintype "passive"))
    )
    (net (code "46") (name "Net-(C48-Pad2)") (class "Default")
      (node (ref "C48") (pin "2") (pinfunction "2_2") (pintype "passive"))
      (node (ref "C49") (pin "1") (pinfunction "1_1") (pintype "passive"))
    )
    (net (code "47") (name "Net-(C49-Pad2)") (class "Default")
      (node (ref "C49") (pin "2") (pinfunction "2_2") (pintype "passive"))
      (node (ref "C50") (pin "1") (pinfunction "1_1") (pintype "passive"))
    )
    (net (code "48") (name "Net-(C50-Pad2)") (class "Default")
      (node (ref "C50") (pin "2") (pinfunction "2_2") (pintype "passive"))
      (node (ref "C51") (pin "1") (pinfunction "1_1") (pintype "passive"))
    )
    (net (code "49") (name "Net-(C52-Pad2)") (class "Default")
      (node (ref "C52") (pin "2") (pinfunction "2_2") (pintype "passive"))
      (node (ref "C53") (pin "1") (pinfunction "1_1") (pintype "passive"))
    )
    (net (code "50") (name "Net-(C53-Pad2)") (class "Default")
      (node (ref "C53") (pin "2") (pinfunction "2_2") (pintype "passive"))
      (node (ref "C54") (pin "1") (pinfunction "1_1") (pintype "passive"))
    )
    (net (code "51") (name "Net-(C54-Pad2)") (class "Default")
      (node (ref "C54") (pin "2") (pinfunction "2_2") (pintype "passive"))
      (node (ref "C55") (pin "1") (pinfunction "1_1") (pintype "passive"))
    )
    (net (code "52") (name "Net-(C55-Pad2)") (class "Default")
      (node (ref "C55") (pin "2") (pinfunction "2_2") (pintype "passive"))
      (node (ref "C56") (pin "1") (pinfunction "1_1") (pintype "passive"))
    )
    (net (code "53") (name "Net-(C56-Pad2)") (class "Default")
      (node (ref "C56") (pin "2") (pinfunction "2_2") (pintype "passive"))
      (node (ref "C57") (pin "1") (pinfunction "1_1") (pintype "passive"))
    )
    (net (code "54") (name "Net-(C57-Pad2)") (class "Default")
      (node (ref "C57") (pin "2") (pinfunction "2_2") (pintype "passive"))
      (node (ref "C58") (pin "1") (pinfunction "1_1") (pintype "passive"))
    )
    (net (code "55") (name "Net-(C58-Pad2)") (class "Default")
      (node (ref "C58") (pin "2") (pinfunction "2_2") (pintype "passive"))
      (node (ref "C59") (pin "1") (pinfunction "1_1") (pintype "passive"))
    )
    (net (code "56") (name "Net-(C59-Pad2)") (class "Default")
      (node (ref "C59") (pin "2") (pinfunction "2_2") (pintype "passive"))
      (node (ref "C60") (pin "1") (pinfunction "1_1") (pintype "passive"))
    )
    (net (code "57") (name "Net-(C60-Pad2)") (class "Default")
      (node (ref "C60") (pin "2") (pinfunction "2_2") (pintype "passive"))
      (node (ref "C61") (pin "1") (pinfunction "1_1") (pintype "passive"))
    )
    (net (code "58") (name "Net-(C61-Pad2)") (class "Default")
      (node (ref "C61") (pin "2") (pinfunction "2_2") (pintype "passive"))
      (node (ref "C62") (pin "1") (pinfunction "1_1") (pintype "passive"))
    )
    (net (code "59") (name "Net-(C62-Pad2)") (class "Default")
      (node (ref "C62") (pin "2") (pinfunction "2_2") (pintype "passive"))
      (node (ref "C63") (pin "1") (pinfunction "1_1") (pintype "passive"))
    )
    (net (code "60") (name "Net-(C63-Pad2)") (class "Default")
      (node (ref "C63") (pin "2") (pinfunction "2_2") (pintype "passive"))
      (node (ref "C64") (pin "1") (pinfunction "1_1") (pintype "passive"))
    )
    (net (code "61") (name "Net-(C64-Pad2)") (class "Default")
      (node (ref "C64") (pin "2") (pinfunction "2_2") (pintype "passive"))
      (node (ref "C65") (pin "1") (pinfunction "1_1") (pintype "passive"))
    )
    (net (code "62") (name "Net-(C65-Pad2)") (class "Default")
      (node (ref "C65") (pin "2") (pinfunction "2_2") (pintype "passive"))
      (node (ref "C66") (pin "1") (pinfunction "1_1") (pintype "passive"))
    )
    (net (code "63") (name "Net-(C66-Pad2)") (class "Default")
      (node (ref "C66") (pin "2") (pinfunction "2_2") (pintype "passive"))
      (node (ref "C67") (pin "1") (pinfunction "1_1") (pintype "passive"))
    )
    (net (code "64") (name "Net-(C67-Pad2)") (class "Default")
      (node (ref "C67") (pin "2") (pinfunction "2_2") (pintype "passive"))
      (node (ref "C68") (pin "1") (pinfunction "1_1") (pintype "passive"))
    )
    (net (code "65") (name "Net-(C69-Pad2)") (class "Default")
      (node (ref "C69") (pin "2") (pinfunction "2_2") (pintype "passive"))
      (node (ref "C70") (pin "1") (pinfunction "1_1") (pintype "passive"))
    )
    (net (code "66") (name "Net-(C70-Pad2)") (class "Default")
      (node (ref "C70") (pin "2") (pinfunction "2_2") (pintype "passive"))
      (node (ref "C71") (pin "1") (pinfunction "1_1") (pintype "passive"))
    )
    (net (code "67") (name "Net-(C71-Pad2)") (class "Default")
      (node (ref "C71") (pin "2") (pinfunction "2_2") (pintype "passive"))
      (node (ref "C72") (pin "1") (pinfunction "1_1") (pintype "passive"))
    )
    (net (code "68") (name "Net-(C72-Pad2)") (class "Default")
      (node (ref "C72") (pin "2") (pinfunction "2_2") (pintype "passive"))
      (node (ref "C73") (pin "1") (pinfunction "1_1") (pintype "passive"))
    )
    (net (code "69") (name "Net-(C73-Pad2)") (class "Default")
      (node (ref "C73") (pin "2") (pinfunction "2_2") (pintype "passive"))
      (node (ref "C74") (pin "1") (pinfunction "1_1") (pintype "passive"))
    )
    (net (code "70") (name "Net-(C74-Pad2)") (class "Default")
      (node (ref "C74") (pin "2") (pinfunction "2_2") (pintype "passive"))
      (node (ref "C75") (pin "1") (pinfunction "1_1") (pintype "passive"))
    )
    (net (code "71") (name "Net-(C75-Pad2)") (class "Default")
      (node (ref "C75") (pin "2") (pinfunction "2_2") (pintype "passive"))
      (node (ref "C76") (pin "1") (pinfunction "1_1") (pintype "passive"))
    )
    (net (code "72") (name "Net-(C76-Pad2)") (class "Default")
      (node (ref "C76") (pin "2") (pinfunction "2_2") (pintype "passive"))
      (node (ref "C77") (pin "1") (pinfunction "1_1") (pintype "passive"))
    )
    (net (code "73") (name "Net-(C77-Pad2)") (class "Default")
      (node (ref "C77") (pin "2") (pinfunction "2_2") (pintype "passive"))
      (node (ref "C78") (pin "1") (pinfunction "1_1") (pintype "passive"))
    )
    (net (code "74") (name "Net-(C78-Pad2)") (class "Default")
      (node (ref "C78") (pin "2") (pinfunction "2_2") (pintype "passive"))
      (node (ref "C79") (pin "1") (pinfunction "1_1") (pintype "passive"))
    )
    (net (code "75") (name "Net-(C79-Pad2)") (class "Default")
      (node (ref "C79") (pin "2") (pinfunction "2_2") (pintype "passive"))
      (node (ref "C80") (pin "1") (pinfunction "1_1") (pintype "passive"))
    )
    (net (code "76") (name "Net-(C80-Pad2)") (class "Default")
      (node (ref "C80") (pin "2") (pinfunction "2_2") (pintype "passive"))
      (node (ref "C81") (pin "1") (pinfunction "1_1") (pintype "passive"))
    )
    (net (code "77") (name "Net-(C81-Pad2)") (class "Default")
      (node (ref "C81") (pin "2") (pinfunction "2_2") (pintype "passive"))
      (node (ref "C82") (pin "1") (pinfunction "1_1") (pintype "passive"))
    )
    (net (code "78") (name "Net-(C82-Pad2)") (class "Default")
      (node (ref "C82") (pin "2") (pinfunction "2_2") (pintype "passive"))
      (node (ref "C83") (pin "1") (pinfunction "1_1") (pintype "passive"))
    )
    (net (code "79") (name "Net-(C83-Pad2)") (class "Default")
      (node (ref "C83") (pin "2") (pinfunction "2_2") (pintype "passive"))
      (node (ref "C84") (pin "1") (pinfunction "1_1") (pintype "passive"))
    )
    (net (code "80") (name "Net-(C84-Pad2)") (class "Default")
      (node (ref "C84") (pin "2") (pinfunction "2_2") (pintype "passive"))
      (node (ref "C85") (pin "1") (pinfunction "1_1") (pintype "passive"))
    )
    (net (code "81") (name "Net-(C86-Pad2)") (class "Default")
      (node (ref "C86") (pin "2") (pinfunction "2_2") (pintype "passive"))
      (node (ref "C87") (pin "1") (pinfunction "1_1") (pintype "passive"))
    )
    (net (code "82") (name "Net-(C87-Pad2)") (class "Default")
      (node (ref "C87") (pin "2") (pinfunction "2_2") (pintype "passive"))
      (node (ref "C88") (pin "1") (pinfunction "1_1") (pintype "passive"))
    )
    (net (code "83") (name "Net-(C88-Pad2)") (class "Default")
      (node (ref "C88") (pin "2") (pinfunction "2_2") (pintype "passive"))
      (node (ref "C89") (pin "1") (pinfunction "1_1") (pintype "passive"))
    )
    (net (code "84") (name "Net-(C89-Pad2)") (class "Default")
      (node (ref "C89") (pin "2") (pinfunction "2_2") (pintype "passive"))
      (node (ref "C90") (pin "1") (pinfunction "1_1") (pintype "passive"))
    )
    (net (code "85") (name "Net-(C90-Pad2)") (class "Default")
      (node (ref "C90") (pin "2") (pinfunction "2_2") (pintype "passive"))
      (node (ref "C91") (pin "1") (pinfunction "1_1") (pintype "passive"))
    )
    (net (code "86") (name "Net-(C91-Pad2)") (class "Default")
      (node (ref "C91") (pin "2") (pinfunction "2_2") (pintype "passive"))
      (node (ref "C92") (pin "1") (pinfunction "1_1") (pintype "passive"))
    )
    (net (code "87") (name "Net-(C92-Pad2)") (class "Default")
      (node (ref "C92") (pin "2") (pinfunction "2_2") (pintype "passive"))
      (node (ref "C93") (pin "1") (pinfunction "1_1") (pintype "passive"))
    )
    (net (code "88") (name "Net-(C93-Pad2)") (class "Default")
      (node (ref "C93") (pin "2") (pinfunction "2_2") (pintype "passive"))
      (node (ref "C94") (pin "1") (pinfunction "1_1") (pintype "passive"))
    )
    (net (code "89") (name "Net-(C94-Pad2)") (class "Default")
      (node (ref "C94") (pin "2") (pinfunction "2_2") (pintype "passive"))
      (node (ref "C95") (pin "1") (pinfunction "1_1") (pintype "passive"))
    )
    (net (code "90") (name "Net-(C95-Pad2)") (class "Default")
      (node (ref "C95") (pin "2") (pinfunction "2_2") (pintype "passive"))
      (node (ref "C96") (pin "1") (pinfunction "1_1") (pintype "passive"))
    )
    (net (code "91") (name "Net-(C96-Pad2)") (class "Default")
      (node (ref "C96") (pin "2") (pinfunction "2_2") (pintype "passive"))
      (node (ref "C97") (pin "1") (pinfunction "1_1") (pintype "passive"))
    )
    (net (code "92") (name "Net-(C97-Pad2)") (class "Default")
      (node (ref "C97") (pin "2") (pinfunction "2_2") (pintype "passive"))
      (node (ref "C98") (pin "1") (pinfunction "1_1") (pintype "passive"))
    )
    (net (code "93") (name "Net-(C98-Pad2)") (class "Default")
      (node (ref "C98") (pin "2") (pinfunction "2_2") (pintype "passive"))
      (node (ref "C99") (pin "1") (pinfunction "1_1") (pintype "passive"))
    )
    (net (code "94") (name "Net-(C100-Pad1)") (class "Default")
      (node (ref "C100") (pin "1") (pinfunction "1_1") (pintype "passive"))
      (node (ref "C99") (pin "2") (pinfunction "2_2") (pintype "passive"))
    )
    (net (code "95") (name "Net-(C100-Pad2)") (class "Default")
      (node (ref "C100") (pin "2") (pinfunction "2_2") (pintype "passive"))
      (node (ref "C101") (pin "1") (pinfunction "1_1") (pintype "passive"))
    )
    (net (code "96") (name "Net-(C101-Pad2)") (class "Default")
      (node (ref "C101") (pin "2") (pinfunction "2_2") (pintype "passive"))
      (node (ref "C102") (pin "1") (pinfunction "1_1") (pintype "passive"))
    )
    (net (code "97") (name "Net-(C103-Pad2)") (class "Default")
      (node (ref "C103") (pin "2") (pinfunction "2_2") (pintype "passive"))
      (node (ref "C104") (pin "1") (pinfunction "1_1") (pintype "passive"))
    )
    (net (code "98") (name "Net-(C104-Pad2)") (class "Default")
      (node (ref "C104") (pin "2") (pinfunction "2_2") (pintype "passive"))
      (node (ref "C105") (pin "1") (pinfunction "1_1") (pintype "passive"))
    )
    (net (code "99") (name "Net-(C105-Pad2)") (class "Default")
      (node (ref "C105") (pin "2") (pinfunction "2_2") (pintype "passive"))
      (node (ref "C106") (pin "1") (pinfunction "1_1") (pintype "passive"))
    )
    (net (code "100") (name "Net-(C106-Pad2)") (class "Default")
      (node (ref "C106") (pin "2") (pinfunction "2_2") (pintype "passive"))
      (node (ref "C107") (pin "1") (pinfunction "1_1") (pintype "passive"))
    )
    (net (code "101") (name "Net-(C107-Pad2)") (class "Default")
      (node (ref "C107") (pin "2") (pinfunction "2_2") (pintype "passive"))
      (node (ref "C108") (pin "1") (pinfunction "1_1") (pintype "passive"))
    )
    (net (code "102") (name "Net-(C108-Pad2)") (class "Default")
      (node (ref "C108") (pin "2") (pinfunction "2_2") (pintype "passive"))
      (node (ref "C109") (pin "1") (pinfunction "1_1") (pintype "passive"))
    )
    (net (code "103") (name "Net-(C109-Pad2)") (class "Default")
      (node (ref "C109") (pin "2") (pinfunction "2_2") (pintype "passive"))
      (node (ref "C110") (pin "1") (pinfunction "1_1") (pintype "passive"))
    )
    (net (code "104") (name "Net-(C110-Pad2)") (class "Default")
      (node (ref "C110") (pin "2") (pinfunction "2_2") (pintype "passive"))
      (node (ref "C111") (pin "1") (pinfunction "1_1") (pintype "passive"))
    )
    (net (code "105") (name "Net-(C111-Pad2)") (class "Default")
      (node (ref "C111") (pin "2") (pinfunction "2_2") (pintype "passive"))
      (node (ref "C112") (pin "1") (pinfunction "1_1") (pintype "passive"))
    )
    (net (code "106") (name "Net-(C112-Pad2)") (class "Default")
      (node (ref "C112") (pin "2") (pinfunction "2_2") (pintype "passive"))
      (node (ref "C113") (pin "1") (pinfunction "1_1") (pintype "passive"))
    )
    (net (code "107") (name "Net-(C113-Pad2)") (class "Default")
      (node (ref "C113") (pin "2") (pinfunction "2_2") (pintype "passive"))
      (node (ref "C114") (pin "1") (pinfunction "1_1") (pintype "passive"))
    )
    (net (code "108") (name "Net-(C114-Pad2)") (class "Default")
      (node (ref "C114") (pin "2") (pinfunction "2_2") (pintype "passive"))
      (node (ref "C115") (pin "1") (pinfunction "1_1") (pintype "passive"))
    )
    (net (code "109") (name "Net-(C115-Pad2)") (class "Default")
      (node (ref "C115") (pin "2") (pinfunction "2_2") (pintype "passive"))
      (node (ref "C116") (pin "1") (pinfunction "1_1") (pintype "passive"))
    )
    (net (code "110") (name "Net-(C116-Pad2)") (class "Default")
      (node (ref "C116") (pin "2") (pinfunction "2_2") (pintype "passive"))
      (node (ref "C117") (pin "1") (pinfunction "1_1") (pintype "passive"))
    )
    (net (code "111") (name "Net-(C117-Pad2)") (class "Default")
      (node (ref "C117") (pin "2") (pinfunction "2_2") (pintype "passive"))
      (node (ref "C118") (pin "1") (pinfunction "1_1") (pintype "passive"))
    )
    (net (code "112") (name "Net-(C118-Pad2)") (class "Default")
      (node (ref "C118") (pin "2") (pinfunction "2_2") (pintype "passive"))
      (node (ref "C119") (pin "1") (pinfunction "1_1") (pintype "passive"))
    )
    (net (code "113") (name "Net-(C120-Pad2)") (class "Default")
      (node (ref "C120") (pin "2") (pinfunction "2_2") (pintype "passive"))
      (node (ref "C121") (pin "1") (pinfunction "1_1") (pintype "passive"))
    )
    (net (code "114") (name "Net-(C121-Pad2)") (class "Default")
      (node (ref "C121") (pin "2") (pinfunction "2_2") (pintype "passive"))
      (node (ref "C122") (pin "1") (pinfunction "1_1") (pintype "passive"))
    )
    (net (code "115") (name "Net-(C122-Pad2)") (class "Default")
      (node (ref "C122") (pin "2") (pinfunction "2_2") (pintype "passive"))
      (node (ref "C123") (pin "1") (pinfunction "1_1") (pintype "passive"))
    )
    (net (code "116") (name "Net-(C123-Pad2)") (class "Default")
      (node (ref "C123") (pin "2") (pinfunction "2_2") (pintype "passive"))
      (node (ref "C124") (pin "1") (pinfunction "1_1") (pintype "passive"))
    )
    (net (code "117") (name "Net-(C124-Pad2)") (class "Default")
      (node (ref "C124") (pin "2") (pinfunction "2_2") (pintype "passive"))
      (node (ref "C125") (pin "1") (pinfunction "1_1") (pintype "passive"))
    )
    (net (code "118") (name "Net-(C125-Pad2)") (class "Default")
      (node (ref "C125") (pin "2") (pinfunction "2_2") (pintype "passive"))
      (node (ref "C126") (pin "1") (pinfunction "1_1") (pintype "passive"))
    )
    (net (code "119") (name "Net-(C126-Pad2)") (class "Default")
      (node (ref "C126") (pin "2") (pinfunction "2_2") (pintype "passive"))
      (node (ref "C127") (pin "1") (pinfunction "1_1") (pintype "passive"))
    )
    (net (code "120") (name "Net-(C127-Pad2)") (class "Default")
      (node (ref "C127") (pin "2") (pinfunction "2_2") (pintype "passive"))
      (node (ref "C128") (pin "1") (pinfunction "1_1") (pintype "passive"))
    )
    (net (code "121") (name "Net-(C128-Pad2)") (class "Default")
      (node (ref "C128") (pin "2") (pinfunction "2_2") (pintype "passive"))
      (node (ref "C129") (pin "1") (pinfunction "1_1") (pintype "passive"))
    )
    (net (code "122") (name "Net-(C129-Pad2)") (class "Default")
      (node (ref "C129") (pin "2") (pinfunction "2_2") (pintype "passive"))
      (node (ref "C130") (pin "1") (pinfunction "1_1") (pintype "passive"))
    )
    (net (code "123") (name "Net-(C130-Pad2)") (class "Default")
      (node (ref "C130") (pin "2") (pinfunction "2_2") (pintype "passive"))
      (node (ref "C131") (pin "1") (pinfunction "1_1") (pintype "passive"))
    )
    (net (code "124") (name "Net-(C131-Pad2)") (class "Default")
      (node (ref "C131") (pin "2") (pinfunction "2_2") (pintype "passive"))
      (node (ref "C132") (pin "1") (pinfunction "1_1") (pintype "passive"))
    )
    (net (code "125") (name "Net-(C132-Pad2)") (class "Default")
      (node (ref "C132") (pin "2") (pinfunction "2_2") (pintype "passive"))
      (node (ref "C133") (pin "1") (pinfunction "1_1") (pintype "passive"))
    )
    (net (code "126") (name "Net-(C133-Pad2)") (class "Default")
      (node (ref "C133") (pin "2") (pinfunction "2_2") (pintype "passive"))
      (node (ref "C134") (pin "1") (pinfunction "1_1") (pintype "passive"))
    )
    (net (code "127") (name "Net-(C134-Pad2)") (class "Default")
      (node (ref "C134") (pin "2") (pinfunction "2_2") (pintype "passive"))
      (node (ref "C135") (pin "1") (pinfunction "1_1") (pintype "passive"))
    )
    (net (code "128") (name "Net-(C135-Pad2)") (class "Default")
      (node (ref "C135") (pin "2") (pinfunction "2_2") (pintype "passive"))
      (node (ref "C136") (pin "1") (pinfunction "1_1") (pintype "passive"))
    )
    (net (code "129") (name "Net-(C137-Pad1)") (class "Default")
      (node (ref "C137") (pin "1") (pinfunction "1_1") (pintype "passive"))
      (node (ref "C138") (pin "1") (pinfunction "1_1") (pintype "passive"))
      (node (ref "C139") (pin "1") (pinfunction "1_1") (pintype "passive"))
      (node (ref "C140") (pin "1") (pinfunction "1_1") (pintype "passive"))
      (node (ref "C141") (pin "1") (pinfunction "1_1") (pintype "passive"))
      (node (ref "C142") (pin "1") (pinfunction "1_1") (pintype "passive"))
      (node (ref "C143") (pin "1") (pinfunction "1_1") (pintype "passive"))
      (node (ref "C144") (pin "1") (pinfunction "1_1") (pintype "passive"))
      (node (ref "C145") (pin "1") (pinfunction "1_1") (pintype "passive"))
      (node (ref "C146") (pin "1") (pinfunction "1_1") (pintype "passive"))
      (node (ref "C147") (pin "1") (pinfunction "1_1") (pintype "passive"))
      (node (ref "C148") (pin "1") (pinfunction "1_1") (pintype "passive"))
      (node (ref "C149") (pin "1") (pinfunction "1_1") (pintype "passive"))
      (node (ref "C150") (pin "1") (pinfunction "1_1") (pintype "passive"))
      (node (ref "C151") (pin "1") (pinfunction "1_1") (pintype "passive"))
      (node (ref "C152") (pin "1") (pinfunction "1_1") (pintype "passive"))
      (node (ref "C153") (pin "1") (pinfunction "1_1") (pintype "passive"))
      (node (ref "C154") (pin "1") (pinfunction "1_1") (pintype "passive"))
    )
    (net (code "130") (name "Net-(C137-Pad2)") (class "Default")
      (node (ref "C137") (pin "2") (pinfunction "2_2") (pintype "passive"))
      (node (ref "C138") (pin "2") (pinfunction "2_2") (pintype "passive"))
      (node (ref "C139") (pin "2") (pinfunction "2_2") (pintype "passive"))
      (node (ref "C140") (pin "2") (pinfunction "2_2") (pintype "passive"))
      (node (ref "C141") (pin "2") (pinfunction "2_2") (pintype "passive"))
      (node (ref "C142") (pin "2") (pinfunction "2_2") (pintype "passive"))
      (node (ref "C143") (pin "2") (pinfunction "2_2") (pintype "passive"))
      (node (ref "C144") (pin "2") (pinfunction "2_2") (pintype "passive"))
      (node (ref "C145") (pin "2") (pinfunction "2_2") (pintype "passive"))
      (node (ref "C146") (pin "2") (pinfunction "2_2") (pintype "passive"))
      (node (ref "C147") (pin "2") (pinfunction "2_2") (pintype "passive"))
      (node (ref "C148") (pin "2") (pinfunction "2_2") (pintype "passive"))
      (node (ref "C149") (pin "2") (pinfunction "2_2") (pintype "passive"))
      (node (ref "C150") (pin "2") (pinfunction "2_2") (pintype "passive"))
      (node (ref "C151") (pin "2") (pinfunction "2_2") (pintype "passive"))
      (node (ref "C152") (pin "2") (pinfunction "2_2") (pintype "passive"))
      (node (ref "C153") (pin "2") (pinfunction "2_2") (pintype "passive"))
      (node (ref "C154") (pin "2") (pinfunction "2_2") (pintype "passive"))
    )
    (net (code "131") (name "Net-(C155-Pad1)") (class "Default")
      (node (ref "C155") (pin "1") (pinfunction "1_1") (pintype "passive"))
      (node (ref "C156") (pin "1") (pinfunction "1_1") (pintype "passive"))
      (node (ref "C157") (pin "1") (pinfunction "1_1") (pintype "passive"))
      (node (ref "C158") (pin "1") (pinfunction "1_1") (pintype "passive"))
      (node (ref "C159") (pin "1") (pinfunction "1_1") (pintype "passive"))
      (node (ref "C160") (pin "1") (pinfunction "1_1") (pintype "passive"))
      (node (ref "C161") (pin "1") (pinfunction "1_1") (pintype "passive"))
      (node (ref "C162") (pin "1") (pinfunction "1_1") (pintype "passive"))
      (node (ref "C163") (pin "1") (pinfunction "1_1") (pintype "passive"))
      (node (ref "C164") (pin "1") (pinfunction "1_1") (pintype "passive"))
      (node (ref "C165") (pin "1") (pinfunction "1_1") (pintype "passive"))
      (node (ref "C166") (pin "1") (pinfunction "1_1") (pintype "passive"))
      (node (ref "C167") (pin "1") (pinfunction "1_1") (pintype "passive"))
      (node (ref "C168") (pin "1") (pinfunction "1_1") (pintype "passive"))
      (node (ref "C169") (pin "1") (pinfunction "1_1") (pintype "passive"))
      (node (ref "C170") (pin "1") (pinfunction "1_1") (pintype "passive"))
      (node (ref "C171") (pin "1") (pinfunction "1_1") (pintype "passive"))
      (node (ref "C172") (pin "1") (pinfunction "1_1") (pintype "passive"))
    )
    (net (code "132") (name "Net-(C155-Pad2)") (class "Default")
      (node (ref "C155") (pin "2") (pinfunction "2_2") (pintype "passive"))
      (node (ref "C156") (pin "2") (pinfunction "2_2") (pintype "passive"))
      (node (ref "C157") (pin "2") (pinfunction "2_2") (pintype "passive"))
      (node (ref "C158") (pin "2") (pinfunction "2_2") (pintype "passive"))
      (node (ref "C159") (pin "2") (pinfunction "2_2") (pintype "passive"))
      (node (ref "C160") (pin "2") (pinfunction "2_2") (pintype "passive"))
      (node (ref "C161") (pin "2") (pinfunction "2_2") (pintype "passive"))
      (node (ref "C162") (pin "2") (pinfunction "2_2") (pintype "passive"))
      (node (ref "C163") (pin "2") (pinfunction "2_2") (pintype "passive"))
      (node (ref "C164") (pin "2") (pinfunction "2_2") (pintype "passive"))
      (node (ref "C165") (pin "2") (pinfunction "2_2") (pintype "passive"))
      (node (ref "C166") (pin "2") (pinfunction "2_2") (pintype "passive"))
      (node (ref "C167") (pin "2") (pinfunction "2_2") (pintype "passive"))
      (node (ref "C168") (pin "2") (pinfunction "2_2") (pintype "passive"))
      (node (ref "C169") (pin "2") (pinfunction "2_2") (pintype "passive"))
      (node (ref "C170") (pin "2") (pinfunction "2_2") (pintype "passive"))
      (node (ref "C171") (pin "2") (pinfunction "2_2") (pintype "passive"))
      (node (ref "C172") (pin "2") (pinfunction "2_2") (pintype "passive"))
    )
    (net (code "133") (name "unconnected-(C1-Pad1)") (class "Default")
      (node (ref "C1") (pin "1") (pinfunction "1_1") (pintype "passive"))
    )
    (net (code "134") (name "unconnected-(C17-Pad2)") (class "Default")
      (node (ref "C17") (pin "2") (pinfunction "2_2") (pintype "passive"))
    )
    (net (code "135") (name "unconnected-(C18-Pad1)") (class "Default")
      (node (ref "C18") (pin "1") (pinfunction "1_1") (pintype "passive"))
    )
    (net (code "136") (name "unconnected-(C34-Pad2)") (class "Default")
      (node (ref "C34") (pin "2") (pinfunction "2_2") (pintype "passive"))
    )
    (net (code "137") (name "unconnected-(C35-Pad1)") (class "Default")
      (node (ref "C35") (pin "1") (pinfunction "1_1") (pintype "passive"))
    )
    (net (code "138") (name "unconnected-(C51-Pad2)") (class "Default")
      (node (ref "C51") (pin "2") (pinfunction "2_2") (pintype "passive"))
    )
    (net (code "139") (name "unconnected-(C52-Pad1)") (class "Default")
      (node (ref "C52") (pin "1") (pinfunction "1_1") (pintype "passive"))
    )
    (net (code "140") (name "unconnected-(C68-Pad2)") (class "Default")
      (node (ref "C68") (pin "2") (pinfunction "2_2") (pintype "passive"))
    )
    (net (code "141") (name "unconnected-(C69-Pad1)") (class "Default")
      (node (ref "C69") (pin "1") (pinfunction "1_1") (pintype "passive"))
    )
    (net (code "142") (name "unconnected-(C85-Pad2)") (class "Default")
      (node (ref "C85") (pin "2") (pinfunction "2_2") (pintype "passive"))
    )
    (net (code "143") (name "unconnected-(C86-Pad1)") (class "Default")
      (node (ref "C86") (pin "1") (pinfunction "1_1") (pintype "passive"))
    )
    (net (code "144") (name "unconnected-(C102-Pad2)") (class "Default")
      (node (ref "C102") (pin "2") (pinfunction "2_2") (pintype "passive"))
    )
    (net (code "145") (name "unconnected-(C103-Pad1)") (class "Default")
      (node (ref "C103") (pin "1") (pinfunction "1_1") (pintype "passive"))
    )
    (net (code "146") (name "unconnected-(C119-Pad2)") (class "Default")
      (node (ref "C119") (pin "2") (pinfunction "2_2") (pintype "passive"))
    )
    (net (code "147") (name "unconnected-(C120-Pad1)") (class "Default")
      (node (ref "C120") (pin "1") (pinfunction "1_1") (pintype "passive"))
    )
    (net (code "148") (name "unconnected-(C136-Pad2)") (class "Default")
      (node (ref "C136") (pin "2") (pinfunction "2_2") (pintype "passive"))
    )
  )
)
